# XT_NANO_DOCK.net
KiCad netlist of a schematic drawn in Altium Designer
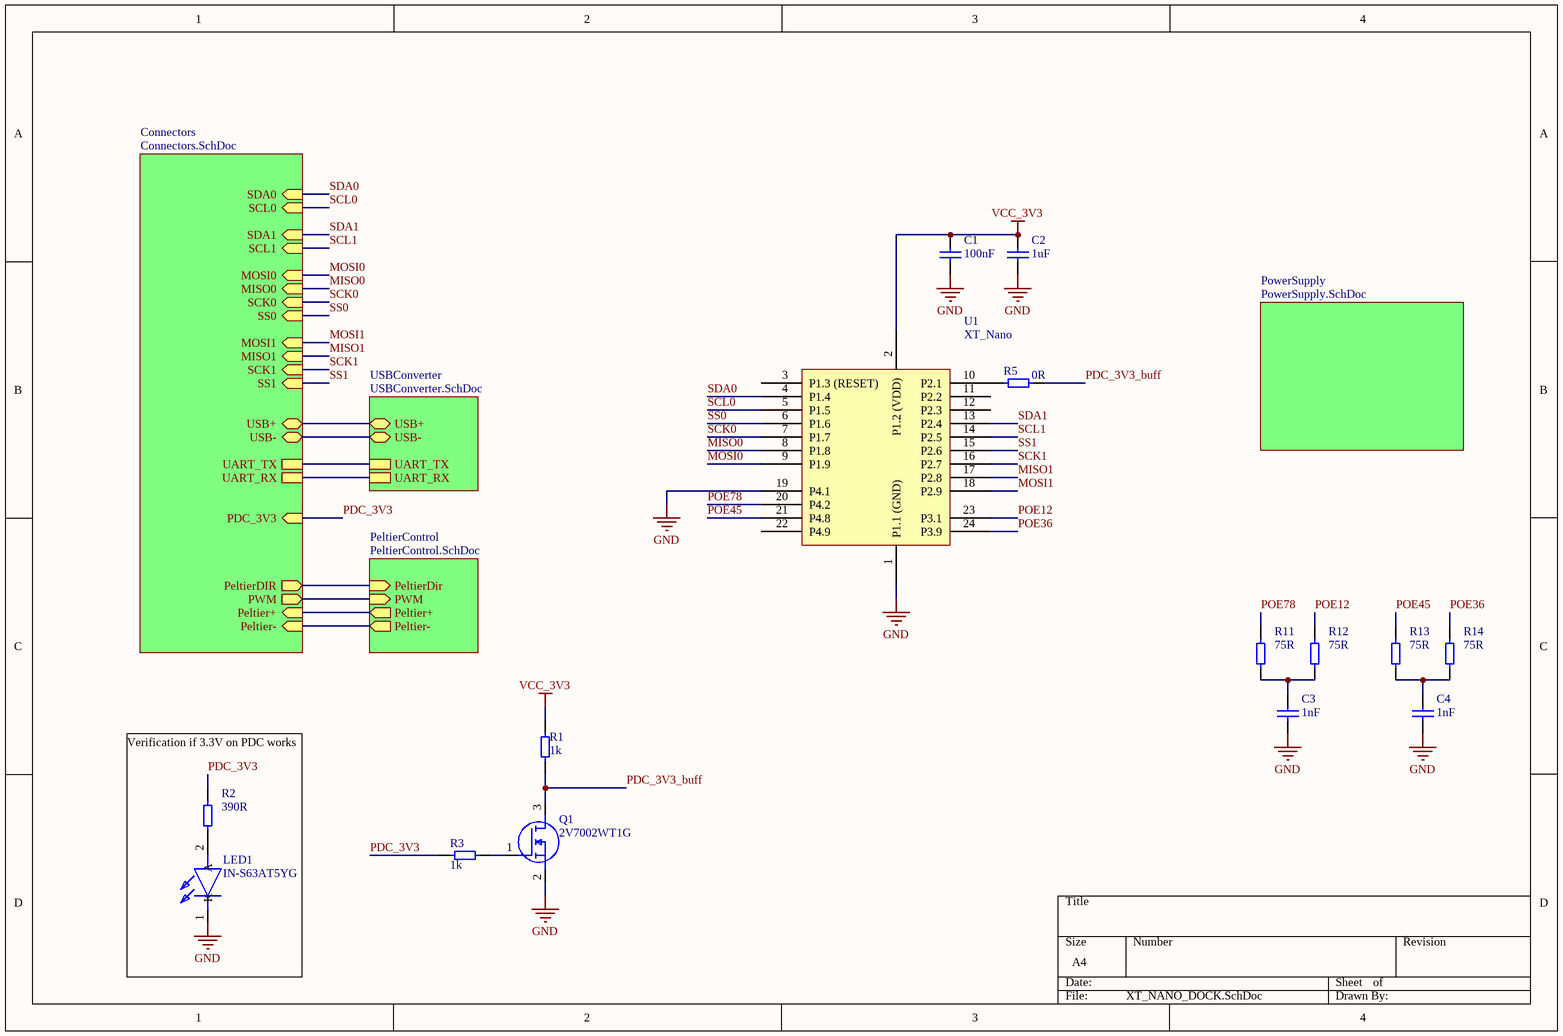
[diagram p0: XT_NANO_DOCK.SchDoc]

(export (version "E")
  (design (tool "Eeschema 10.0.6"))
  (components
    (comp (ref "C1")
      (value "100nF")
      (footprint "0603-Capacitor")
      (description "Capacitor")
      (fields (field (name "PART NUMBER") "C0603"))
      (libsource (lib "ZUIAM_LIB") (part "Capacitor"))
    )
    (comp (ref "C2")
      (value "1uF")
      (footprint "0603-Capacitor")
      (description "Capacitor")
      (fields (field (name "PART NUMBER") "C0603"))
      (libsource (lib "ZUIAM_LIB") (part "Capacitor"))
    )
    (comp (ref "C3")
      (value "1nF")
      (footprint "0603-Capacitor")
      (description "Capacitor")
      (fields (field (name "PART NUMBER") "C0603"))
      (libsource (lib "ZUIAM_LIB") (part "Capacitor"))
    )
    (comp (ref "C4")
      (value "1nF")
      (footprint "0603-Capacitor")
      (description "Capacitor")
      (fields (field (name "PART NUMBER") "C0603"))
      (libsource (lib "ZUIAM_LIB") (part "Capacitor"))
    )
    (comp (ref "LED1")
      (value "IN-S63AT5YG")
      (footprint "LEDM168X39N")
      (description "LED")
      (fields (field (name "MOUSER PART NUMBER") "743-IN-S63AT5G"))
      (libsource (lib "mouser") (part "IN-S63AT5G"))
    )
    (comp (ref "Q1")
      (value "2V7002WT1G")
      (footprint "MouserDropbox:SOT65P220X100-3N")
      (description "MOSFET (N-Channel)")
      (fields (field (name "MOUSER PART NUMBER") "863-2V7002WT1G") (field (name "RS PART NUMBER") "7905246P"))
      (libsource (lib "*") (part "2V7002WT1G"))
    )
    (comp (ref "R1")
      (value "1k")
      (footprint "0603-Resistor")
      (description "Resistor")
      (fields (field (name "PART NUMBER") "R0603"))
      (libsource (lib "") (part "Resistor_2"))
    )
    (comp (ref "R2")
      (value "390R")
      (footprint "0603-Resistor")
      (description "Resistor")
      (fields (field (name "PART NUMBER") "R0603"))
      (libsource (lib "") (part "Resistor_1"))
    )
    (comp (ref "R3")
      (value "1k")
      (footprint "0603-Resistor")
      (description "Resistor")
      (fields (field (name "PART NUMBER") "R0603"))
      (libsource (lib "ZUIAM_LIB") (part "Resistor"))
    )
    (comp (ref "R5")
      (value "0R")
      (footprint "0603-Resistor")
      (description "Resistor")
      (fields (field (name "PART NUMBER") "R0603"))
      (libsource (lib "ZUIAM_LIB") (part "Resistor"))
    )
    (comp (ref "R11")
      (value "75R")
      (footprint "0603-Resistor")
      (description "Resistor")
      (fields (field (name "PART NUMBER") "R0603"))
      (libsource (lib "") (part "Resistor_1"))
    )
    (comp (ref "R12")
      (value "75R")
      (footprint "0603-Resistor")
      (description "Resistor")
      (fields (field (name "PART NUMBER") "R0603"))
      (libsource (lib "") (part "Resistor_1"))
    )
    (comp (ref "R13")
      (value "75R")
      (footprint "0603-Resistor")
      (description "Resistor")
      (fields (field (name "PART NUMBER") "R0603"))
      (libsource (lib "") (part "Resistor_1"))
    )
    (comp (ref "R14")
      (value "75R")
      (footprint "0603-Resistor")
      (description "Resistor")
      (fields (field (name "PART NUMBER") "R0603"))
      (libsource (lib "") (part "Resistor_1"))
    )
    (comp (ref "U1")
      (value "XT_Nano")
      (footprint "XT-PICO")
      (description "XT nano module by ak-nord")
      (fields (field (name "MANUFACTURER") "Ak-nord"))
      (libsource (lib "externalModules") (part "XT_Nano"))
    )
  )
  (nets
    (net (code "1") (name "/MISO0") (class "Default")
      (node (ref "U1") (pin "8") (pinfunction "P1.8_8") (pintype "passive"))
    )
    (net (code "2") (name "/MISO1") (class "Default")
      (node (ref "U1") (pin "17") (pinfunction "P2.8_17") (pintype "passive"))
    )
    (net (code "3") (name "/MOSI0") (class "Default")
      (node (ref "U1") (pin "9") (pinfunction "P1.9_9") (pintype "passive"))
    )
    (net (code "4") (name "/MOSI1") (class "Default")
      (node (ref "U1") (pin "18") (pinfunction "P2.9_18") (pintype "passive"))
    )
    (net (code "5") (name "/PDC_3V3") (class "Default")
      (node (ref "R2") (pin "2") (pinfunction "2_2") (pintype "passive"))
      (node (ref "R3") (pin "2") (pinfunction "2_2") (pintype "passive"))
    )
    (net (code "6") (name "/PDC_3V3_buff") (class "Default")
      (node (ref "Q1") (pin "3") (pinfunction "D_3") (pintype "passive"))
      (node (ref "R1") (pin "2") (pinfunction "2_2") (pintype "passive"))
      (node (ref "R5") (pin "1") (pinfunction "1_1") (pintype "passive"))
    )
    (net (code "7") (name "/POE12") (class "Default")
      (node (ref "R12") (pin "2") (pinfunction "2_2") (pintype "passive"))
      (node (ref "U1") (pin "23") (pinfunction "P3.1_23") (pintype "passive"))
    )
    (net (code "8") (name "/POE36") (class "Default")
      (node (ref "R14") (pin "2") (pinfunction "2_2") (pintype "passive"))
      (node (ref "U1") (pin "24") (pinfunction "P3.9_24") (pintype "passive"))
    )
    (net (code "9") (name "/POE45") (class "Default")
      (node (ref "R13") (pin "2") (pinfunction "2_2") (pintype "passive"))
      (node (ref "U1") (pin "21") (pinfunction "P4.8_21") (pintype "passive"))
    )
    (net (code "10") (name "/POE78") (class "Default")
      (node (ref "R11") (pin "2") (pinfunction "2_2") (pintype "passive"))
      (node (ref "U1") (pin "20") (pinfunction "P4.2_20") (pintype "passive"))
    )
    (net (code "15") (name "/SCK0") (class "Default")
      (node (ref "U1") (pin "7") (pinfunction "P1.7_7") (pintype "passive"))
    )
    (net (code "16") (name "/SCK1") (class "Default")
      (node (ref "U1") (pin "16") (pinfunction "P2.7_16") (pintype "passive"))
    )
    (net (code "17") (name "/SCL0") (class "Default")
      (node (ref "U1") (pin "5") (pinfunction "P1.5_5") (pintype "passive"))
    )
    (net (code "18") (name "/SCL1") (class "Default")
      (node (ref "U1") (pin "14") (pinfunction "P2.5_14") (pintype "passive"))
    )
    (net (code "19") (name "/SDA0") (class "Default")
      (node (ref "U1") (pin "4") (pinfunction "P1.4_4") (pintype "passive"))
    )
    (net (code "20") (name "/SDA1") (class "Default")
      (node (ref "U1") (pin "13") (pinfunction "P2.4_13") (pintype "passive"))
    )
    (net (code "21") (name "/SS0") (class "Default")
      (node (ref "U1") (pin "6") (pinfunction "P1.6_6") (pintype "passive"))
    )
    (net (code "22") (name "/SS1") (class "Default")
      (node (ref "U1") (pin "15") (pinfunction "P2.6_15") (pintype "passive"))
    )
    (net (code "27") (name "GND") (class "Default")
      (node (ref "C1") (pin "2") (pinfunction "2_2") (pintype "passive"))
      (node (ref "C2") (pin "2") (pinfunction "2_2") (pintype "passive"))
      (node (ref "C3") (pin "2") (pinfunction "2_2") (pintype "passive"))
      (node (ref "C4") (pin "2") (pinfunction "2_2") (pintype "passive"))
      (node (ref "LED1") (pin "1") (pinfunction "K_1") (pintype "passive"))
      (node (ref "Q1") (pin "2") (pinfunction "S_2") (pintype "passive"))
      (node (ref "U1") (pin "1") (pinfunction "P1.1_(GND)_1") (pintype "passive"))
      (node (ref "U1") (pin "19") (pinfunction "P4.1_19") (pintype "passive"))
    )
    (net (code "28") (name "Net-(C3-Pad1)") (class "Default")
      (node (ref "C3") (pin "1") (pinfunction "1_1") (pintype "passive"))
      (node (ref "R11") (pin "1") (pinfunction "1_1") (pintype "passive"))
      (node (ref "R12") (pin "1") (pinfunction "1_1") (pintype "passive"))
    )
    (net (code "29") (name "Net-(C4-Pad1)") (class "Default")
      (node (ref "C4") (pin "1") (pinfunction "1_1") (pintype "passive"))
      (node (ref "R13") (pin "1") (pinfunction "1_1") (pintype "passive"))
      (node (ref "R14") (pin "1") (pinfunction "1_1") (pintype "passive"))
    )
    (net (code "30") (name "Net-(LED1-A)") (class "Default")
      (node (ref "LED1") (pin "2") (pinfunction "A_2") (pintype "passive"))
      (node (ref "R2") (pin "1") (pinfunction "1_1") (pintype "passive"))
    )
    (net (code "31") (name "Net-(Q1-G)") (class "Default")
      (node (ref "Q1") (pin "1") (pinfunction "G_1") (pintype "passive"))
      (node (ref "R3") (pin "1") (pinfunction "1_1") (pintype "passive"))
    )
    (net (code "32") (name "Net-(U1-P2.1)") (class "Default")
      (node (ref "R5") (pin "2") (pinfunction "2_2") (pintype "passive"))
      (node (ref "U1") (pin "10") (pinfunction "P2.1_10") (pintype "passive"))
    )
    (net (code "33") (name "VCC_3V3") (class "Default")
      (node (ref "C1") (pin "1") (pinfunction "1_1") (pintype "passive"))
      (node (ref "C2") (pin "1") (pinfunction "1_1") (pintype "passive"))
      (node (ref "R1") (pin "1") (pinfunction "1_1") (pintype "passive"))
      (node (ref "U1") (pin "2") (pinfunction "P1.2_(VDD)_2") (pintype "passive"))
    )
    (net (code "34") (name "unconnected-(U1-P1.3_(RESET)-Pad3)") (class "Default")
      (node (ref "U1") (pin "3") (pinfunction "P1.3_(RESET)_3") (pintype "passive"))
    )
    (net (code "35") (name "unconnected-(U1-P2.2-Pad11)") (class "Default")
      (node (ref "U1") (pin "11") (pinfunction "P2.2_11") (pintype "passive"))
    )
    (net (code "36") (name "unconnected-(U1-P2.3-Pad12)") (class "Default")
      (node (ref "U1") (pin "12") (pinfunction "P2.3_12") (pintype "passive"))
    )
    (net (code "37") (name "unconnected-(U1-P4.9-Pad22)") (class "Default")
      (node (ref "U1") (pin "22") (pinfunction "P4.9_22") (pintype "passive"))
    )
  )
)
